# AC_Motor_Control_Shield.net
KiCad netlist of a schematic drawn in EAGLE
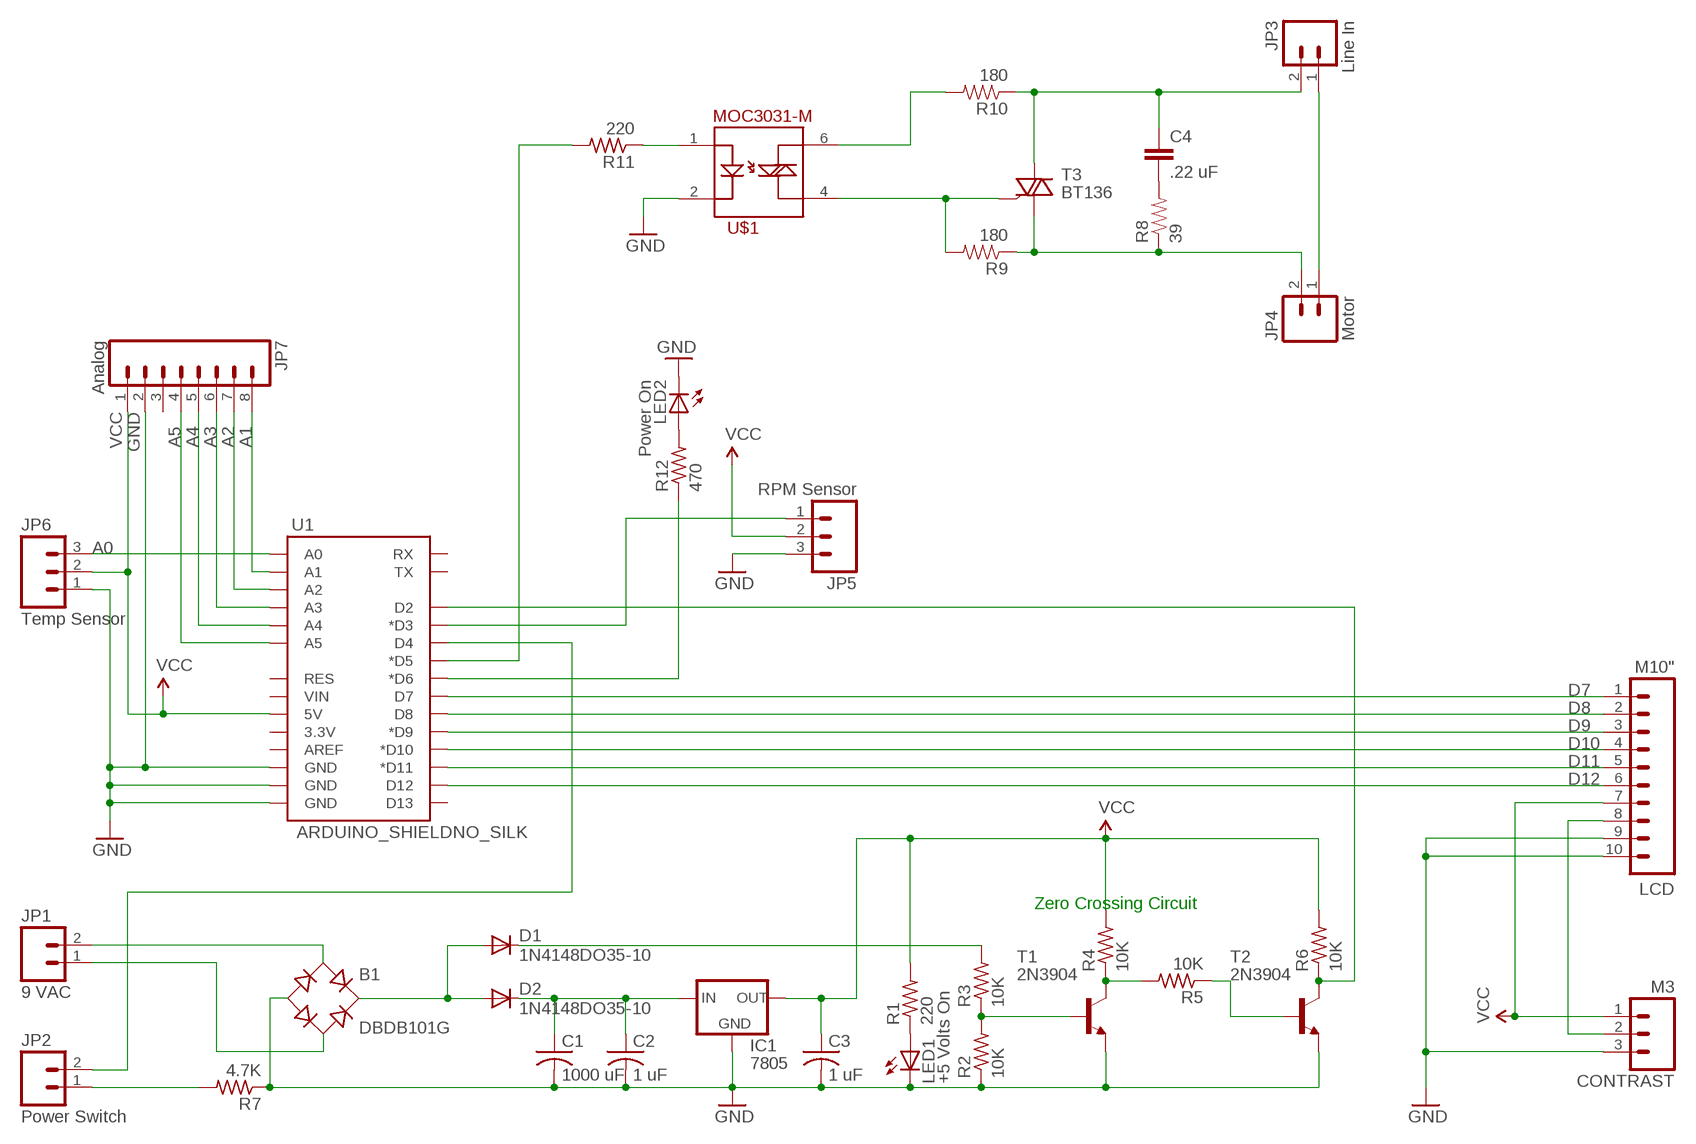
[diagram p0: schematic, sheet 1]

(export (version "E")
  (design (tool "Eeschema 10.0.6"))
  (components
    (comp (ref "B1")
      (value "DBDB101G")
      (footprint "eagle-import:DB")
      (libsource (lib "eagle-import") (part "DB?GDB101"))
    )
    (comp (ref "C1")
      (value "1000 uF")
      (footprint "eagle-import:C050-035X075")
      (libsource (lib "eagle-import") (part "C-US050-035X075"))
    )
    (comp (ref "C2")
      (value "1 uF")
      (footprint "eagle-import:C050-035X075")
      (libsource (lib "eagle-import") (part "C-US050-035X075"))
    )
    (comp (ref "C3")
      (value "1 uF")
      (footprint "eagle-import:C050-035X075")
      (libsource (lib "eagle-import") (part "C-US050-035X075"))
    )
    (comp (ref "C4")
      (value ".22 uF")
      (footprint "eagle-import:CAP-PTH-LARGE")
      (libsource (lib "eagle-import") (part "CAPPTH3"))
    )
    (comp (ref "CONTRAST")
      (value "M3")
      (footprint "eagle-import:1X03")
      (libsource (lib "eagle-import") (part "M03PTH"))
    )
    (comp (ref "D1")
      (value "1N4148DO35-10")
      (footprint "eagle-import:DO35-10")
      (libsource (lib "eagle-import") (part "1N4148DO35-10"))
    )
    (comp (ref "D2")
      (value "1N4148DO35-10")
      (footprint "eagle-import:DO35-10")
      (libsource (lib "eagle-import") (part "1N4148DO35-10"))
    )
    (comp (ref "IC1")
      (value "7805")
      (footprint "eagle-import:TO-220-ALT")
      (libsource (lib "eagle-import") (part "V_REG_78XX-TO-220"))
    )
    (comp (ref "JP1")
      (value "9 VAC")
      (footprint "eagle-import:SCREWTERMINAL-5MM-2")
      (libsource (lib "eagle-import") (part "M025MM"))
    )
    (comp (ref "JP2")
      (value "Power Switch")
      (footprint "eagle-import:1X02")
      (libsource (lib "eagle-import") (part "M02PTH"))
    )
    (comp (ref "JP3")
      (value "Line In")
      (footprint "eagle-import:SCREWTERMINAL-5MM-2")
      (libsource (lib "eagle-import") (part "M025MM"))
    )
    (comp (ref "JP4")
      (value "Motor")
      (footprint "eagle-import:SCREWTERMINAL-5MM-2")
      (libsource (lib "eagle-import") (part "M025MM"))
    )
    (comp (ref "JP5")
      (value "RPM Sensor")
      (footprint "eagle-import:1X03")
      (libsource (lib "eagle-import") (part "M03PTH"))
    )
    (comp (ref "JP6")
      (value "Temp Sensor")
      (footprint "eagle-import:1X03")
      (libsource (lib "eagle-import") (part "M03PTH"))
    )
    (comp (ref "JP7")
      (value "Analog")
      (footprint "eagle-import:1X08")
      (libsource (lib "eagle-import") (part "M081X08"))
    )
    (comp (ref "LCD")
      (value "M10\"")
      (footprint "eagle-import:1X10")
      (libsource (lib "eagle-import") (part "M10{dblquote}"))
    )
    (comp (ref "LED1")
      (value "+5 Volts On")
      (footprint "eagle-import:LED5MM")
      (libsource (lib "eagle-import") (part "LED5MM"))
    )
    (comp (ref "LED2")
      (value "Power On")
      (footprint "eagle-import:LED5MM")
      (libsource (lib "eagle-import") (part "LED5MM"))
    )
    (comp (ref "R1")
      (value "220")
      (footprint "eagle-import:0207_10")
      (libsource (lib "eagle-import") (part "R-US_0207/10"))
    )
    (comp (ref "R2")
      (value "10K")
      (footprint "eagle-import:0207_10")
      (libsource (lib "eagle-import") (part "R-US_0207/10"))
    )
    (comp (ref "R3")
      (value "10K")
      (footprint "eagle-import:0207_10")
      (libsource (lib "eagle-import") (part "R-US_0207/10"))
    )
    (comp (ref "R4")
      (value "10K")
      (footprint "eagle-import:0207_10")
      (libsource (lib "eagle-import") (part "R-US_0207/10"))
    )
    (comp (ref "R5")
      (value "10K")
      (footprint "eagle-import:0207_10")
      (libsource (lib "eagle-import") (part "R-US_0207/10"))
    )
    (comp (ref "R6")
      (value "10K")
      (footprint "eagle-import:0207_10")
      (libsource (lib "eagle-import") (part "R-US_0207/10"))
    )
    (comp (ref "R7")
      (value "4.7K")
      (footprint "eagle-import:0207_10")
      (libsource (lib "eagle-import") (part "R-US_0207/10"))
    )
    (comp (ref "R8")
      (value "39")
      (footprint "eagle-import:AXIAL-0.6")
      (libsource (lib "eagle-import") (part "RESISTORPTH-1W"))
    )
    (comp (ref "R9")
      (value "180")
      (footprint "eagle-import:AXIAL-0.6")
      (libsource (lib "eagle-import") (part "RESISTORPTH-1W"))
    )
    (comp (ref "R10")
      (value "180")
      (footprint "eagle-import:AXIAL-0.6")
      (libsource (lib "eagle-import") (part "RESISTORPTH-1W"))
    )
    (comp (ref "R11")
      (value "220")
      (footprint "eagle-import:0207_10")
      (libsource (lib "eagle-import") (part "R-US_0207/10"))
    )
    (comp (ref "R12")
      (value "470")
      (footprint "eagle-import:0207_10")
      (libsource (lib "eagle-import") (part "R-US_0207/10"))
    )
    (comp (ref "T1")
      (value "2N3904")
      (footprint "eagle-import:TO92")
      (libsource (lib "eagle-import") (part "2N3904"))
    )
    (comp (ref "T2")
      (value "2N3904")
      (footprint "eagle-import:TO92")
      (libsource (lib "eagle-import") (part "2N3904"))
    )
    (comp (ref "T3")
      (value "BT136")
      (footprint "eagle-import:TO220AB")
      (libsource (lib "eagle-import") (part "BT136"))
    )
    (comp (ref "U$1")
      (value "MOC3031-M")
      (footprint "eagle-import:DIL06")
      (libsource (lib "eagle-import") (part "MOC3031-M"))
    )
    (comp (ref "U1")
      (value "ARDUINO_SHIELDNO_SILK")
      (footprint "eagle-import:DUEMILANOVE_VIAS")
      (libsource (lib "eagle-import") (part "ARDUINO_SHIELDNO_SILK"))
    )
  )
  (nets
    (net (code "1") (name "/A0") (class "Default")
      (node (ref "JP6") (pin "3") (pinfunction "3_3") (pintype "passive"))
      (node (ref "U1") (pin "A0") (pinfunction "A0_A0") (pintype "bidirectional"))
    )
    (net (code "2") (name "/A1") (class "Default")
      (node (ref "JP7") (pin "8") (pinfunction "8_8") (pintype "passive"))
      (node (ref "U1") (pin "A1") (pinfunction "A1_A1") (pintype "bidirectional"))
    )
    (net (code "3") (name "/A2") (class "Default")
      (node (ref "JP7") (pin "7") (pinfunction "7_7") (pintype "passive"))
      (node (ref "U1") (pin "A2") (pinfunction "A2_A2") (pintype "bidirectional"))
    )
    (net (code "4") (name "/A3") (class "Default")
      (node (ref "JP7") (pin "6") (pinfunction "6_6") (pintype "passive"))
      (node (ref "U1") (pin "A3") (pinfunction "A3_A3") (pintype "bidirectional"))
    )
    (net (code "5") (name "/A4") (class "Default")
      (node (ref "JP7") (pin "5") (pinfunction "5_5") (pintype "passive"))
      (node (ref "U1") (pin "A4") (pinfunction "A4_A4") (pintype "bidirectional"))
    )
    (net (code "6") (name "/A5") (class "Default")
      (node (ref "JP7") (pin "4") (pinfunction "4_4") (pintype "passive"))
      (node (ref "U1") (pin "A5") (pinfunction "A5_A5") (pintype "bidirectional"))
    )
    (net (code "7") (name "/D7") (class "Default")
      (node (ref "LCD") (pin "1") (pinfunction "1_1") (pintype "passive"))
      (node (ref "U1") (pin "D7") (pinfunction "D7_D7") (pintype "bidirectional"))
    )
    (net (code "8") (name "/D8") (class "Default")
      (node (ref "LCD") (pin "2") (pinfunction "2_2") (pintype "passive"))
      (node (ref "U1") (pin "D8") (pinfunction "D8_D8") (pintype "bidirectional"))
    )
    (net (code "9") (name "/D9") (class "Default")
      (node (ref "LCD") (pin "3") (pinfunction "3_3") (pintype "passive"))
      (node (ref "U1") (pin "D9") (pinfunction "*D9_D9") (pintype "bidirectional"))
    )
    (net (code "10") (name "/D10") (class "Default")
      (node (ref "LCD") (pin "4") (pinfunction "4_4") (pintype "passive"))
      (node (ref "U1") (pin "D10") (pinfunction "*D10_D10") (pintype "bidirectional"))
    )
    (net (code "11") (name "/D11") (class "Default")
      (node (ref "LCD") (pin "5") (pinfunction "5_5") (pintype "passive"))
      (node (ref "U1") (pin "D11") (pinfunction "*D11_D11") (pintype "bidirectional"))
    )
    (net (code "12") (name "/D12") (class "Default")
      (node (ref "LCD") (pin "6") (pinfunction "6_6") (pintype "passive"))
      (node (ref "U1") (pin "D12") (pinfunction "D12_D12") (pintype "bidirectional"))
    )
    (net (code "13") (name "GND") (class "Default")
      (node (ref "B1") (pin "-") (pinfunction "-_-") (pintype "passive"))
      (node (ref "C1") (pin "2") (pinfunction "2_2") (pintype "passive"))
      (node (ref "C2") (pin "2") (pinfunction "2_2") (pintype "passive"))
      (node (ref "C3") (pin "2") (pinfunction "2_2") (pintype "passive"))
      (node (ref "CONTRAST") (pin "3") (pinfunction "3_3") (pintype "passive"))
      (node (ref "IC1") (pin "GND") (pinfunction "GND_GND") (pintype "input"))
      (node (ref "JP5") (pin "3") (pinfunction "3_3") (pintype "passive"))
      (node (ref "JP6") (pin "1") (pinfunction "1_1") (pintype "passive"))
      (node (ref "JP7") (pin "2") (pinfunction "2_2") (pintype "passive"))
      (node (ref "LCD") (pin "10") (pinfunction "10_10") (pintype "passive"))
      (node (ref "LCD") (pin "9") (pinfunction "9_9") (pintype "passive"))
      (node (ref "LED1") (pin "K") (pinfunction "C_K") (pintype "passive"))
      (node (ref "LED2") (pin "K") (pinfunction "C_K") (pintype "passive"))
      (node (ref "R2") (pin "1") (pinfunction "1_1") (pintype "passive"))
      (node (ref "R7") (pin "1") (pinfunction "1_1") (pintype "passive"))
      (node (ref "T1") (pin "3") (pinfunction "E_3") (pintype "passive"))
      (node (ref "T2") (pin "3") (pinfunction "E_3") (pintype "passive"))
      (node (ref "U$1") (pin "2") (pinfunction "2_2") (pintype "bidirectional"))
      (node (ref "U1") (pin "GND@0") (pinfunction "GND_GND@0") (pintype "bidirectional"))
      (node (ref "U1") (pin "GND@1") (pinfunction "GND_GND@1") (pintype "bidirectional"))
      (node (ref "U1") (pin "GND@2") (pinfunction "GND_GND@2") (pintype "bidirectional"))
    )
    (net (code "14") (name "Net-(B1-Pad+)") (class "Default")
      (node (ref "B1") (pin "+") (pinfunction "+_+") (pintype "passive"))
      (node (ref "D1") (pin "A") (pinfunction "A_A") (pintype "passive"))
      (node (ref "D2") (pin "A") (pinfunction "A_A") (pintype "passive"))
    )
    (net (code "15") (name "Net-(B1-PadAC1)") (class "Default")
      (node (ref "B1") (pin "AC1") (pinfunction "AC1_AC1") (pintype "passive"))
      (node (ref "JP1") (pin "2") (pinfunction "2_2") (pintype "passive"))
    )
    (net (code "16") (name "Net-(B1-PadAC2)") (class "Default")
      (node (ref "B1") (pin "AC2") (pinfunction "AC2_AC2") (pintype "passive"))
      (node (ref "JP1") (pin "1") (pinfunction "1_1") (pintype "passive"))
    )
    (net (code "17") (name "Net-(C1-Pad1)") (class "Default")
      (node (ref "C1") (pin "1") (pinfunction "1_1") (pintype "passive"))
      (node (ref "C2") (pin "1") (pinfunction "1_1") (pintype "passive"))
      (node (ref "D2") (pin "C") (pinfunction "C_C") (pintype "passive"))
      (node (ref "IC1") (pin "IN") (pinfunction "IN_IN") (pintype "input"))
    )
    (net (code "18") (name "Net-(CONTRAST-Pad2)") (class "Default")
      (node (ref "CONTRAST") (pin "2") (pinfunction "2_2") (pintype "passive"))
      (node (ref "LCD") (pin "8") (pinfunction "8_8") (pintype "passive"))
    )
    (net (code "19") (name "Net-(D1-PadC)") (class "Default")
      (node (ref "D1") (pin "C") (pinfunction "C_C") (pintype "passive"))
      (node (ref "R3") (pin "2") (pinfunction "2_2") (pintype "passive"))
    )
    (net (code "20") (name "Net-(JP2-Pad1)") (class "Default")
      (node (ref "JP2") (pin "1") (pinfunction "1_1") (pintype "passive"))
      (node (ref "R7") (pin "2") (pinfunction "2_2") (pintype "passive"))
    )
    (net (code "21") (name "Net-(JP2-Pad2)") (class "Default")
      (node (ref "JP2") (pin "2") (pinfunction "2_2") (pintype "passive"))
      (node (ref "U1") (pin "D4") (pinfunction "D4_D4") (pintype "bidirectional"))
    )
    (net (code "22") (name "Net-(JP3-Pad1)") (class "Default")
      (node (ref "JP3") (pin "1") (pinfunction "1_1") (pintype "passive"))
      (node (ref "JP4") (pin "1") (pinfunction "1_1") (pintype "passive"))
    )
    (net (code "23") (name "Net-(LED1-PadA)") (class "Default")
      (node (ref "LED1") (pin "A") (pinfunction "A_A") (pintype "passive"))
      (node (ref "R1") (pin "1") (pinfunction "1_1") (pintype "passive"))
    )
    (net (code "24") (name "Net-(LED2-PadA)") (class "Default")
      (node (ref "LED2") (pin "A") (pinfunction "A_A") (pintype "passive"))
      (node (ref "R12") (pin "2") (pinfunction "2_2") (pintype "passive"))
    )
    (net (code "25") (name "Net-(R8-1)") (class "Default")
      (node (ref "JP4") (pin "2") (pinfunction "2_2") (pintype "passive"))
      (node (ref "R8") (pin "P$1") (pinfunction "1_P$1") (pintype "passive"))
      (node (ref "R9") (pin "P$1") (pinfunction "1_P$1") (pintype "passive"))
      (node (ref "T3") (pin "1") (pinfunction "A1_1") (pintype "passive"))
    )
    (net (code "26") (name "Net-(R8-2)") (class "Default")
      (node (ref "C4") (pin "2") (pinfunction "2_2") (pintype "passive"))
      (node (ref "R8") (pin "P$2") (pinfunction "2_P$2") (pintype "passive"))
    )
    (net (code "27") (name "Net-(R9-2)") (class "Default")
      (node (ref "R9") (pin "P$2") (pinfunction "2_P$2") (pintype "passive"))
      (node (ref "T3") (pin "3") (pinfunction "G_3") (pintype "passive"))
      (node (ref "U$1") (pin "4") (pinfunction "4_4") (pintype "bidirectional"))
    )
    (net (code "28") (name "Net-(R10-1)") (class "Default")
      (node (ref "C4") (pin "1") (pinfunction "1_1") (pintype "passive"))
      (node (ref "JP3") (pin "2") (pinfunction "2_2") (pintype "passive"))
      (node (ref "R10") (pin "P$1") (pinfunction "1_P$1") (pintype "passive"))
      (node (ref "T3") (pin "2") (pinfunction "A2_2") (pintype "passive"))
    )
    (net (code "29") (name "Net-(R10-2)") (class "Default")
      (node (ref "R10") (pin "P$2") (pinfunction "2_P$2") (pintype "passive"))
      (node (ref "U$1") (pin "6") (pinfunction "6_6") (pintype "bidirectional"))
    )
    (net (code "30") (name "Net-(R11-Pad1)") (class "Default")
      (node (ref "R11") (pin "1") (pinfunction "1_1") (pintype "passive"))
      (node (ref "U$1") (pin "1") (pinfunction "1_1") (pintype "bidirectional"))
    )
    (net (code "31") (name "Net-(T1-B)") (class "Default")
      (node (ref "R2") (pin "2") (pinfunction "2_2") (pintype "passive"))
      (node (ref "R3") (pin "1") (pinfunction "1_1") (pintype "passive"))
      (node (ref "T1") (pin "2") (pinfunction "B_2") (pintype "passive"))
    )
    (net (code "32") (name "Net-(T1-C)") (class "Default")
      (node (ref "R4") (pin "1") (pinfunction "1_1") (pintype "passive"))
      (node (ref "R5") (pin "2") (pinfunction "2_2") (pintype "passive"))
      (node (ref "T1") (pin "1") (pinfunction "C_1") (pintype "passive"))
    )
    (net (code "33") (name "Net-(T2-B)") (class "Default")
      (node (ref "R5") (pin "1") (pinfunction "1_1") (pintype "passive"))
      (node (ref "T2") (pin "2") (pinfunction "B_2") (pintype "passive"))
    )
    (net (code "34") (name "Net-(T2-C)") (class "Default")
      (node (ref "R6") (pin "1") (pinfunction "1_1") (pintype "passive"))
      (node (ref "T2") (pin "1") (pinfunction "C_1") (pintype "passive"))
      (node (ref "U1") (pin "D2") (pinfunction "D2_D2") (pintype "bidirectional"))
    )
    (net (code "35") (name "Net-(U1-*D3)") (class "Default")
      (node (ref "JP5") (pin "1") (pinfunction "1_1") (pintype "passive"))
      (node (ref "U1") (pin "D3") (pinfunction "*D3_D3") (pintype "bidirectional"))
    )
    (net (code "36") (name "Net-(U1-*D5)") (class "Default")
      (node (ref "R11") (pin "2") (pinfunction "2_2") (pintype "passive"))
      (node (ref "U1") (pin "D5") (pinfunction "*D5_D5") (pintype "bidirectional"))
    )
    (net (code "37") (name "Net-(U1-*D6)") (class "Default")
      (node (ref "R12") (pin "1") (pinfunction "1_1") (pintype "passive"))
      (node (ref "U1") (pin "D6") (pinfunction "*D6_D6") (pintype "bidirectional"))
    )
    (net (code "38") (name "VCC") (class "Default")
      (node (ref "C3") (pin "1") (pinfunction "1_1") (pintype "passive"))
      (node (ref "CONTRAST") (pin "1") (pinfunction "1_1") (pintype "passive"))
      (node (ref "IC1") (pin "OUT") (pinfunction "OUT_OUT") (pintype "output"))
      (node (ref "JP5") (pin "2") (pinfunction "2_2") (pintype "passive"))
      (node (ref "JP6") (pin "2") (pinfunction "2_2") (pintype "passive"))
      (node (ref "JP7") (pin "1") (pinfunction "1_1") (pintype "passive"))
      (node (ref "LCD") (pin "7") (pinfunction "7_7") (pintype "passive"))
      (node (ref "R1") (pin "2") (pinfunction "2_2") (pintype "passive"))
      (node (ref "R4") (pin "2") (pinfunction "2_2") (pintype "passive"))
      (node (ref "R6") (pin "2") (pinfunction "2_2") (pintype "passive"))
      (node (ref "U1") (pin "5V") (pinfunction "5V_5V") (pintype "bidirectional"))
    )
    (net (code "39") (name "unconnected-(JP7-Pad3)") (class "Default")
      (node (ref "JP7") (pin "3") (pinfunction "3_3") (pintype "passive"))
    )
    (net (code "40") (name "unconnected-(U1-Pad3.3V)") (class "Default")
      (node (ref "U1") (pin "3.3V") (pinfunction "3.3V_3.3V") (pintype "bidirectional"))
    )
    (net (code "41") (name "unconnected-(U1-PadAREF)") (class "Default")
      (node (ref "U1") (pin "AREF") (pinfunction "AREF_AREF") (pintype "bidirectional"))
    )
    (net (code "42") (name "unconnected-(U1-PadD13)") (class "Default")
      (node (ref "U1") (pin "D13") (pinfunction "D13_D13") (pintype "bidirectional"))
    )
    (net (code "43") (name "unconnected-(U1-PadRES)") (class "Default")
      (node (ref "U1") (pin "RES") (pinfunction "RES_RES") (pintype "bidirectional"))
    )
    (net (code "44") (name "unconnected-(U1-PadRX)") (class "Default")
      (node (ref "U1") (pin "RX") (pinfunction "RX_RX") (pintype "bidirectional"))
    )
    (net (code "45") (name "unconnected-(U1-PadTX)") (class "Default")
      (node (ref "U1") (pin "TX") (pinfunction "TX_TX") (pintype "bidirectional"))
    )
    (net (code "46") (name "unconnected-(U1-PadVIN)") (class "Default")
      (node (ref "U1") (pin "VIN") (pinfunction "VIN_VIN") (pintype "bidirectional"))
    )
  )
)
